# MIPI.net
KiCad netlist of a schematic drawn in Altium Designer
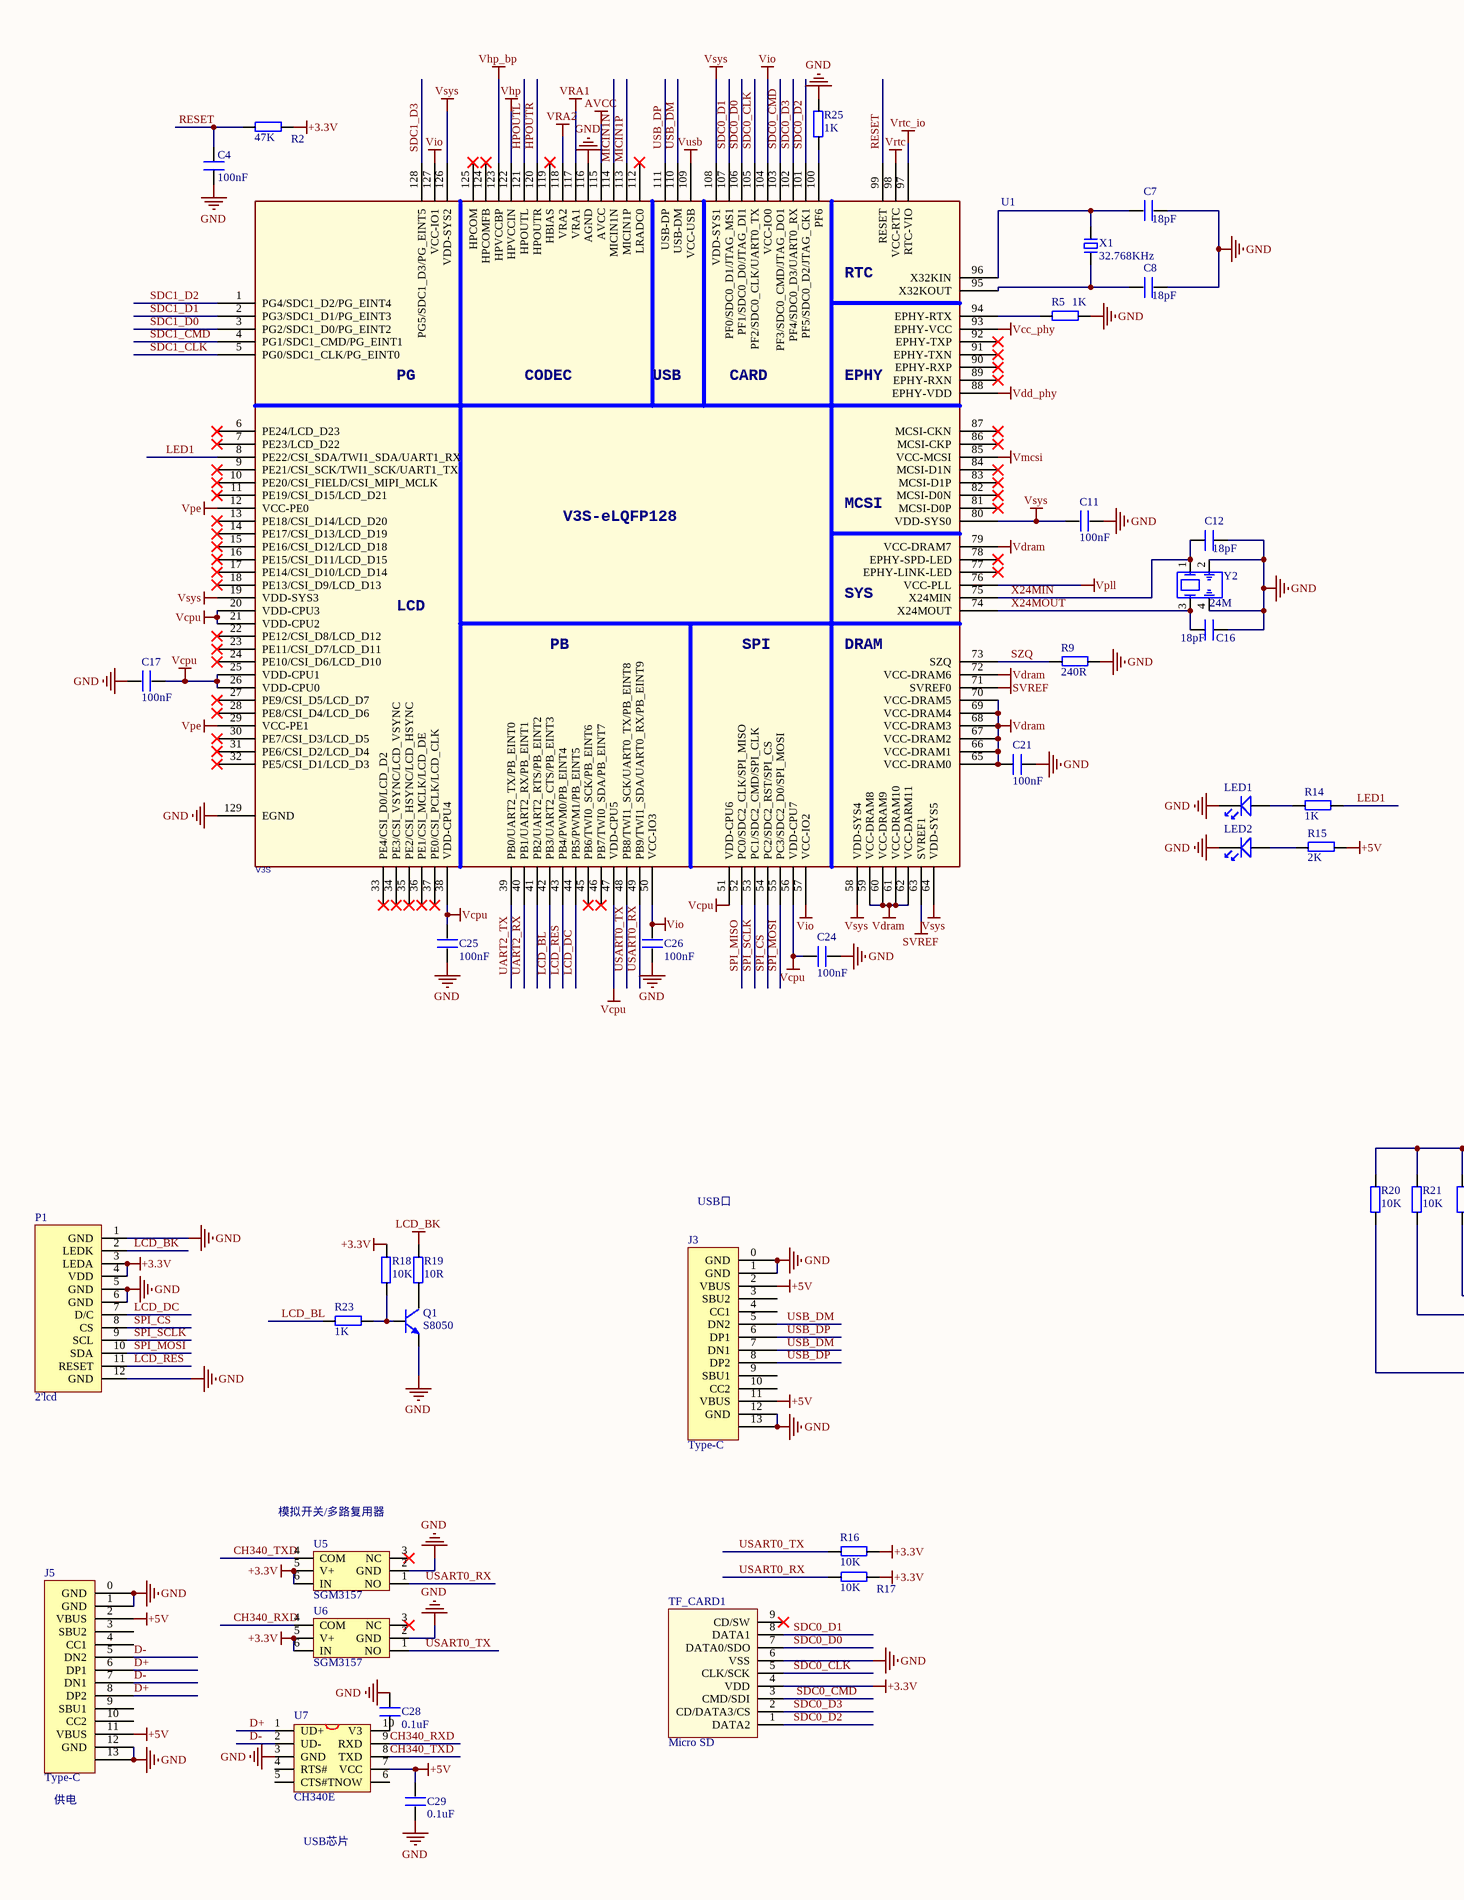
[diagram p0: MIPI.SCHDOC, left]
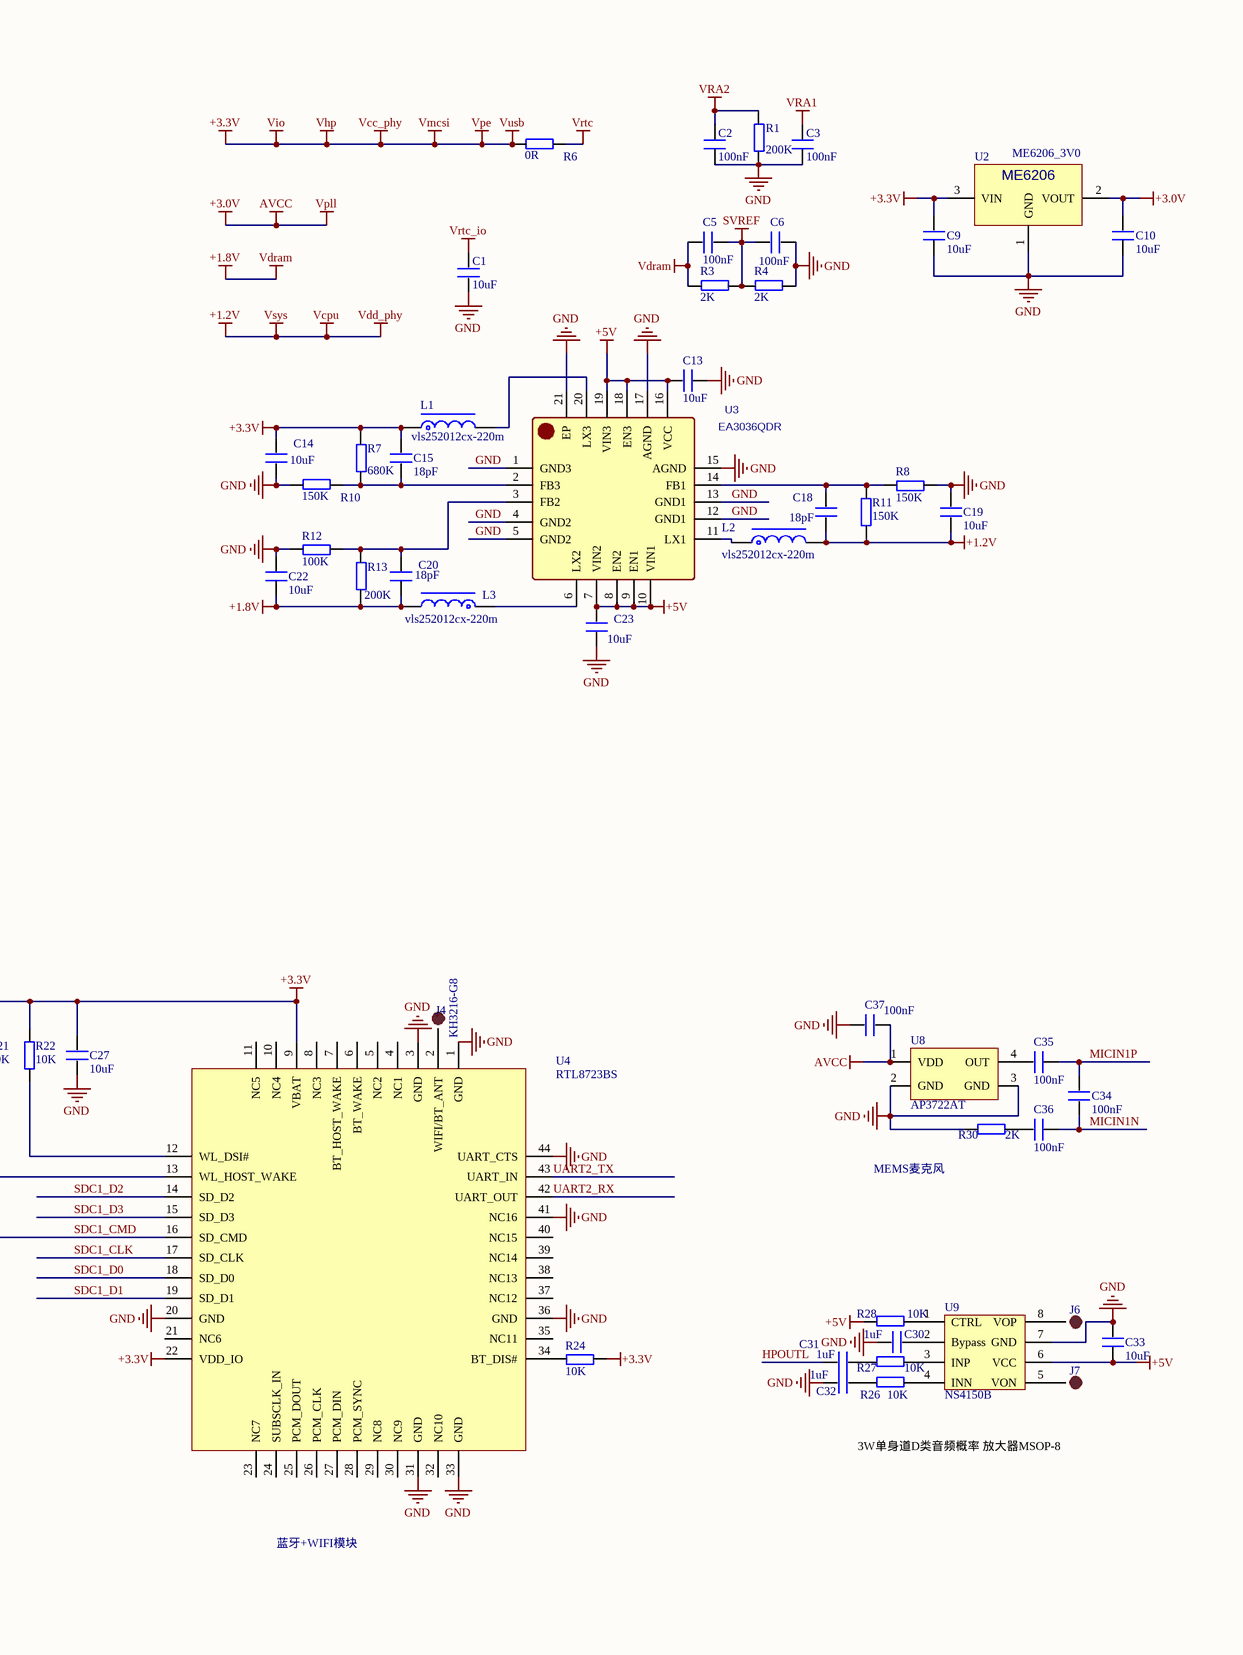
[diagram p1: MIPI.SCHDOC, right]

(export (version "E")
  (design (tool "Eeschema 10.0.6"))
  (components
    (comp (ref "C1") (value "10uF") (footprint "0603") (libsource (lib "AltiumLib") (part "C")))
    (comp (ref "C2") (value "100nF") (footprint "0402") (libsource (lib "AltiumLib") (part "C")))
    (comp (ref "C3") (value "100nF") (footprint "0402") (libsource (lib "AltiumLib") (part "C")))
    (comp (ref "C4") (value "100nF") (footprint "0402") (libsource (lib "AltiumLib") (part "C")))
    (comp (ref "C5") (value "100nF") (footprint "0402") (libsource (lib "AltiumLib") (part "C")))
    (comp (ref "C6") (value "100nF") (footprint "0402") (libsource (lib "AltiumLib") (part "C")))
    (comp (ref "C7") (value "18pF") (footprint "0402") (libsource (lib "AltiumLib") (part "C")))
    (comp (ref "C8") (value "18pF") (footprint "0402") (libsource (lib "AltiumLib") (part "C")))
    (comp (ref "C9") (value "10uF") (footprint "0603") (libsource (lib "AltiumLib") (part "C")))
    (comp (ref "C10") (value "10uF") (footprint "0603") (libsource (lib "AltiumLib") (part "C")))
    (comp (ref "C11") (value "100nF") (footprint "0402") (libsource (lib "AltiumLib") (part "C")))
    (comp (ref "C12") (value "18pF") (footprint "0402") (libsource (lib "AltiumLib") (part "C")))
    (comp (ref "C13") (value "10uF") (footprint "0603") (libsource (lib "AltiumLib") (part "C")))
    (comp (ref "C14") (value "10uF") (footprint "0603") (libsource (lib "AltiumLib") (part "C")))
    (comp (ref "C15") (value "18pF") (footprint "0402") (libsource (lib "AltiumLib") (part "C")))
    (comp (ref "C16") (value "18pF") (footprint "0402") (libsource (lib "AltiumLib") (part "C")))
    (comp (ref "C17") (value "100nF") (footprint "0402") (libsource (lib "AltiumLib") (part "C")))
    (comp (ref "C18") (value "18pF") (footprint "0402") (libsource (lib "AltiumLib") (part "C")))
    (comp (ref "C19") (value "10uF") (footprint "0603") (libsource (lib "AltiumLib") (part "C")))
    (comp (ref "C20") (value "18pF") (footprint "0402") (libsource (lib "AltiumLib") (part "C")))
    (comp (ref "C21") (value "100nF") (footprint "0402") (libsource (lib "AltiumLib") (part "C")))
    (comp (ref "C22") (value "10uF") (footprint "0603") (libsource (lib "AltiumLib") (part "C")))
    (comp (ref "C23") (value "10uF") (footprint "0603") (libsource (lib "AltiumLib") (part "C")))
    (comp (ref "C24") (value "100nF") (footprint "0402") (libsource (lib "AltiumLib") (part "C")))
    (comp (ref "C25") (value "100nF") (footprint "0402") (libsource (lib "AltiumLib") (part "C")))
    (comp (ref "C26") (value "100nF") (footprint "0402") (libsource (lib "AltiumLib") (part "C")))
    (comp (ref "C27") (value "10uF") (footprint "0603") (libsource (lib "AltiumLib") (part "C")))
    (comp (ref "C28") (value "0.1uF") (footprint "0402") (libsource (lib "AltiumLib") (part "C")))
    (comp (ref "C29") (value "0.1uF") (footprint "0402") (libsource (lib "AltiumLib") (part "C")))
    (comp (ref "C30") (value "1uF") (footprint "0402") (libsource (lib "AltiumLib") (part "C")))
    (comp (ref "C31") (value "1uF") (footprint "0402") (libsource (lib "AltiumLib") (part "C")))
    (comp (ref "C32") (value "1uF") (footprint "0402") (libsource (lib "AltiumLib") (part "C")))
    (comp (ref "C33") (value "10uF") (footprint "0603") (libsource (lib "AltiumLib") (part "C")))
    (comp (ref "C34") (value "100nF") (footprint "0402") (libsource (lib "AltiumLib") (part "C")))
    (comp (ref "C35") (value "100nF") (footprint "0402") (libsource (lib "AltiumLib") (part "C")))
    (comp (ref "C36") (value "100nF") (footprint "0402") (libsource (lib "AltiumLib") (part "C")))
    (comp (ref "C37") (value "100nF") (footprint "0402") (libsource (lib "AltiumLib") (part "C")))
    (comp (ref "J3")
      (value "Type-C")
      (footprint "USB-C-SMD_TYC-302-16")
      (libsource (lib "AltiumLib") (part "Type-C_12pin"))
    )
    (comp (ref "J4")
      (value "KH3216-G8")
      (footprint "ANT-SMD_L3.2-W1.6")
      (description "测试点")
      (libsource (lib "AltiumLib") (part "TEST-POINT"))
    )
    (comp (ref "J5")
      (value "Type-C")
      (footprint "USB-C-SMD_TYC-302-16")
      (libsource (lib "AltiumLib") (part "Type-C_12pin"))
    )
    (comp (ref "J6")
      (value "~")
      (footprint "TP-1.5")
      (description "测试点")
      (libsource (lib "AltiumLib") (part "TEST-POINT"))
    )
    (comp (ref "J7")
      (value "~")
      (footprint "TP-1.5")
      (description "测试点")
      (libsource (lib "AltiumLib") (part "TEST-POINT"))
    )
    (comp (ref "L1")
      (value "vls252012cx-220m")
      (footprint "L1")
      (description "功率屏蔽电感")
      (libsource (lib "AltiumLib") (part "L-CDRH"))
    )
    (comp (ref "L2")
      (value "vls252012cx-220m")
      (footprint "L1")
      (description "功率屏蔽电感")
      (libsource (lib "AltiumLib") (part "L-CDRH"))
    )
    (comp (ref "L3")
      (value "vls252012cx-220m")
      (footprint "L1")
      (description "功率屏蔽电感")
      (libsource (lib "") (part "L-CDRH_1"))
    )
    (comp (ref "LED1") (value "LED") (footprint "0603") (libsource (lib "AltiumLib") (part "LED")))
    (comp (ref "LED2") (value "LED") (footprint "0603") (libsource (lib "AltiumLib") (part "LED")))
    (comp (ref "P1") (value "2'lcd") (footprint "2'LCD") (libsource (lib "AltiumLib") (part "2'lcd")))
    (comp (ref "Q1")
      (value "S8050")
      (footprint "SOT23-3L")
      (description "高频放大-NPN型")
      (libsource (lib "AltiumLib") (part "8050-SMD"))
    )
    (comp (ref "R1") (value "200K") (footprint "0402") (libsource (lib "AltiumLib") (part "R")))
    (comp (ref "R2") (value "47K") (footprint "0402") (libsource (lib "AltiumLib") (part "R")))
    (comp (ref "R3") (value "2K") (footprint "0402") (libsource (lib "AltiumLib") (part "R")))
    (comp (ref "R4") (value "2K") (footprint "0402") (libsource (lib "AltiumLib") (part "R")))
    (comp (ref "R5") (value "1K") (footprint "0402") (libsource (lib "AltiumLib") (part "R")))
    (comp (ref "R6") (value "0R") (footprint "0402") (libsource (lib "AltiumLib") (part "R")))
    (comp (ref "R7") (value "680K") (footprint "0402") (libsource (lib "AltiumLib") (part "R")))
    (comp (ref "R8") (value "150K") (footprint "0402") (libsource (lib "AltiumLib") (part "R")))
    (comp (ref "R9") (value "240R") (footprint "0402") (libsource (lib "AltiumLib") (part "R")))
    (comp (ref "R10") (value "150K") (footprint "0402") (libsource (lib "AltiumLib") (part "R")))
    (comp (ref "R11") (value "150K") (footprint "0402") (libsource (lib "AltiumLib") (part "R")))
    (comp (ref "R12") (value "100K") (footprint "0402") (libsource (lib "AltiumLib") (part "R")))
    (comp (ref "R13") (value "200K") (footprint "0402") (libsource (lib "AltiumLib") (part "R")))
    (comp (ref "R14") (value "1K") (footprint "0402") (libsource (lib "AltiumLib") (part "R")))
    (comp (ref "R15") (value "2K") (footprint "0402") (libsource (lib "AltiumLib") (part "R")))
    (comp (ref "R16") (value "10K") (footprint "0402") (libsource (lib "AltiumLib") (part "R")))
    (comp (ref "R17") (value "10K") (footprint "0402") (libsource (lib "AltiumLib") (part "R")))
    (comp (ref "R18") (value "10K") (footprint "0402") (libsource (lib "AltiumLib") (part "R")))
    (comp (ref "R19") (value "10R") (footprint "0603") (libsource (lib "AltiumLib") (part "R")))
    (comp (ref "R20") (value "10K") (footprint "0402") (libsource (lib "AltiumLib") (part "R")))
    (comp (ref "R21") (value "10K") (footprint "0402") (libsource (lib "AltiumLib") (part "R")))
    (comp (ref "R22") (value "10K") (footprint "0402") (libsource (lib "AltiumLib") (part "R")))
    (comp (ref "R23") (value "1K") (footprint "0402") (libsource (lib "AltiumLib") (part "R")))
    (comp (ref "R24") (value "10K") (footprint "0402") (libsource (lib "AltiumLib") (part "R")))
    (comp (ref "R25") (value "1K") (footprint "0402") (libsource (lib "AltiumLib") (part "R")))
    (comp (ref "R26") (value "10K") (footprint "0402") (libsource (lib "AltiumLib") (part "R")))
    (comp (ref "R27") (value "10K") (footprint "0402") (libsource (lib "AltiumLib") (part "R")))
    (comp (ref "R28") (value "10K") (footprint "0402") (libsource (lib "AltiumLib") (part "R")))
    (comp (ref "R30") (value "2K") (footprint "0402") (libsource (lib "AltiumLib") (part "R")))
    (comp (ref "TF_CARD1")
      (value "Micro SD")
      (footprint "Micro SD")
      (description "Micro SD卡")
      (libsource (lib "AltiumLib") (part "Micro SD"))
    )
    (comp (ref "U1") (value "V3S") (footprint "LQFP-128") (libsource (lib "AltiumLib") (part "V3S")))
    (comp (ref "U2") (value "ME6206_3V0") (footprint "SOT-23") (libsource (lib "AltiumLib") (part "ME6206")))
    (comp (ref "U3")
      (value "EA3036QDR")
      (footprint "TQFN-20")
      (fields (field (name "BOM_SUPPLIER PART") "C111587"))
      (libsource (lib "AltiumLib") (part "EA3036QDR"))
    )
    (comp (ref "U4")
      (value "RTL8723BS")
      (footprint "RTL8723BS")
      (libsource (lib "AltiumLib") (part "RTL8723BS"))
    )
    (comp (ref "U5")
      (value "SGM3157")
      (footprint "SOT363-6L")
      (description "单路双掷模拟开关")
      (libsource (lib "imx6ull_bb") (part "SGM3157"))
    )
    (comp (ref "U6")
      (value "SGM3157")
      (footprint "SOT363-6L")
      (description "单路双掷模拟开关")
      (libsource (lib "imx6ull_bb") (part "SGM3157"))
    )
    (comp (ref "U7")
      (value "CH340E")
      (footprint "MSOP-10")
      (description "USB2UART")
      (libsource (lib "AltiumLib") (part "CH340E"))
    )
    (comp (ref "U8")
      (value "AP3722AT")
      (footprint "AP3722AT")
      (libsource (lib "AltiumLib") (part "AP3722AT"))
    )
    (comp (ref "U9") (value "NS4150B") (footprint "MSOP8") (libsource (lib "AltiumLib") (part "NS4150B")))
    (comp (ref "X1")
      (value "32.768KHz")
      (footprint "XT_3215_2")
      (description "2脚无源晶振")
      (libsource (lib "AltiumLib") (part "XTAL-2P"))
    )
    (comp (ref "Y2") (value "24M") (footprint "X3225") (libsource (lib "AltiumLib") (part "SMD XTAL")))
  )
  (nets
    (net (code "1") (name "+1.2V") (class "Default")
      (node (ref "C11") (pin "2") (pintype "passive"))
      (node (ref "C17") (pin "1") (pintype "passive"))
      (node (ref "C18") (pin "2") (pintype "passive"))
      (node (ref "C19") (pin "2") (pintype "passive"))
      (node (ref "C24") (pin "2") (pintype "passive"))
      (node (ref "C25") (pin "1") (pintype "passive"))
      (node (ref "L2") (pin "2") (pinfunction "2_2") (pintype "passive"))
      (node (ref "R11") (pin "2") (pintype "passive"))
      (node (ref "U1") (pin "108") (pinfunction "VDD-SYS1_108") (pintype "passive"))
      (node (ref "U1") (pin "126") (pinfunction "VDD-SYS2_126") (pintype "passive"))
      (node (ref "U1") (pin "19") (pinfunction "VDD-SYS3_19") (pintype "passive"))
      (node (ref "U1") (pin "20") (pinfunction "VDD-CPU3_20") (pintype "passive"))
      (node (ref "U1") (pin "21") (pinfunction "VDD-CPU2_21") (pintype "passive"))
      (node (ref "U1") (pin "25") (pinfunction "VDD-CPU1_25") (pintype "passive"))
      (node (ref "U1") (pin "26") (pinfunction "VDD-CPU0_26") (pintype "passive"))
      (node (ref "U1") (pin "38") (pinfunction "VDD-CPU4_38") (pintype "passive"))
      (node (ref "U1") (pin "47") (pinfunction "VDD-CPU5_47") (pintype "passive"))
      (node (ref "U1") (pin "51") (pinfunction "VDD-CPU6_51") (pintype "passive"))
      (node (ref "U1") (pin "56") (pinfunction "VDD-CPU7_56") (pintype "passive"))
      (node (ref "U1") (pin "58") (pinfunction "VDD-SYS4_58") (pintype "passive"))
      (node (ref "U1") (pin "64") (pinfunction "VDD-SYS5_64") (pintype "passive"))
      (node (ref "U1") (pin "80") (pinfunction "VDD-SYS0_80") (pintype "passive"))
      (node (ref "U1") (pin "88") (pinfunction "EPHY-VDD_88") (pintype "passive"))
    )
    (net (code "2") (name "+1.8V") (class "Default")
      (node (ref "C20") (pin "2") (pintype "passive"))
      (node (ref "C21") (pin "2") (pintype "passive"))
      (node (ref "C22") (pin "2") (pintype "passive"))
      (node (ref "C5") (pin "2") (pintype "passive"))
      (node (ref "L3") (pin "2") (pinfunction "2_2") (pintype "passive"))
      (node (ref "R13") (pin "2") (pintype "passive"))
      (node (ref "R3") (pin "2") (pintype "passive"))
      (node (ref "U1") (pin "59") (pinfunction "VCC-DRAM8_59") (pintype "passive"))
      (node (ref "U1") (pin "60") (pinfunction "VCC-DRAM9_60") (pintype "passive"))
      (node (ref "U1") (pin "61") (pinfunction "VCC-DRAM10_61") (pintype "passive"))
      (node (ref "U1") (pin "62") (pinfunction "VCC-DARM11_62") (pintype "passive"))
      (node (ref "U1") (pin "65") (pinfunction "VCC-DRAM0_65") (pintype "passive"))
      (node (ref "U1") (pin "66") (pinfunction "VCC-DRAM1_66") (pintype "passive"))
      (node (ref "U1") (pin "67") (pinfunction "VCC-DRAM2_67") (pintype "passive"))
      (node (ref "U1") (pin "68") (pinfunction "VCC-DRAM3_68") (pintype "passive"))
      (node (ref "U1") (pin "69") (pinfunction "VCC-DRAM4_69") (pintype "passive"))
      (node (ref "U1") (pin "70") (pinfunction "VCC-DRAM5_70") (pintype "passive"))
      (node (ref "U1") (pin "72") (pinfunction "VCC-DRAM6_72") (pintype "passive"))
      (node (ref "U1") (pin "79") (pinfunction "VCC-DRAM7_79") (pintype "passive"))
    )
    (net (code "3") (name "+3.0V") (class "Default")
      (node (ref "C10") (pin "1") (pintype "passive"))
      (node (ref "C37") (pin "1") (pintype "passive"))
      (node (ref "U1") (pin "115") (pinfunction "AVCC_115") (pintype "passive"))
      (node (ref "U1") (pin "76") (pinfunction "VCC-PLL_76") (pintype "passive"))
      (node (ref "U2") (pin "2") (pinfunction "VOUT_2") (pintype "power_in"))
      (node (ref "U8") (pin "1") (pinfunction "VDD_1") (pintype "passive"))
    )
    (net (code "4") (name "+3.3V") (class "Default")
      (node (ref "C14") (pin "2") (pintype "passive"))
      (node (ref "C15") (pin "2") (pintype "passive"))
      (node (ref "C26") (pin "2") (pintype "passive"))
      (node (ref "C27") (pin "1") (pintype "passive"))
      (node (ref "C9") (pin "1") (pintype "passive"))
      (node (ref "L1") (pin "1") (pinfunction "1_1") (pintype "passive"))
      (node (ref "P1") (pin "3") (pinfunction "LEDA_3") (pintype "passive"))
      (node (ref "P1") (pin "4") (pinfunction "VDD_4") (pintype "passive"))
      (node (ref "R16") (pin "1") (pintype "passive"))
      (node (ref "R17") (pin "1") (pintype "passive"))
      (node (ref "R18") (pin "1") (pintype "passive"))
      (node (ref "R2") (pin "1") (pintype "passive"))
      (node (ref "R20") (pin "1") (pintype "passive"))
      (node (ref "R21") (pin "1") (pintype "passive"))
      (node (ref "R22") (pin "1") (pintype "passive"))
      (node (ref "R24") (pin "2") (pintype "passive"))
      (node (ref "R6") (pin "2") (pintype "passive"))
      (node (ref "R7") (pin "2") (pintype "passive"))
      (node (ref "TF_CARD1") (pin "4") (pinfunction "VDD_4") (pintype "passive"))
      (node (ref "U1") (pin "104") (pinfunction "VCC-IO0_104") (pintype "passive"))
      (node (ref "U1") (pin "109") (pinfunction "VCC-USB_109") (pintype "passive"))
      (node (ref "U1") (pin "12") (pinfunction "VCC-PE0_12") (pintype "passive"))
      (node (ref "U1") (pin "122") (pinfunction "HPVCCIN_122") (pintype "passive"))
      (node (ref "U1") (pin "127") (pinfunction "VCC-IO1_127") (pintype "passive"))
      (node (ref "U1") (pin "29") (pinfunction "VCC-PE1_29") (pintype "passive"))
      (node (ref "U1") (pin "50") (pinfunction "VCC-IO3_50") (pintype "passive"))
      (node (ref "U1") (pin "57") (pinfunction "VCC-IO2_57") (pintype "passive"))
      (node (ref "U1") (pin "85") (pinfunction "VCC-MCSI_85") (pintype "passive"))
      (node (ref "U1") (pin "93") (pinfunction "EPHY-VCC_93") (pintype "passive"))
      (node (ref "U2") (pin "3") (pinfunction "VIN_3") (pintype "power_in"))
      (node (ref "U4") (pin "22") (pinfunction "VDD_IO_22") (pintype "passive"))
      (node (ref "U4") (pin "9") (pinfunction "VBAT_9") (pintype "passive"))
      (node (ref "U5") (pin "5") (pinfunction "V+_5") (pintype "passive"))
      (node (ref "U5") (pin "6") (pinfunction "IN_6") (pintype "passive"))
      (node (ref "U6") (pin "5") (pinfunction "V+_5") (pintype "passive"))
      (node (ref "U6") (pin "6") (pinfunction "IN_6") (pintype "passive"))
    )
    (net (code "5") (name "+5V") (class "Default")
      (node (ref "C13") (pin "2") (pintype "passive"))
      (node (ref "C23") (pin "2") (pintype "passive"))
      (node (ref "C29") (pin "2") (pintype "passive"))
      (node (ref "C33") (pin "1") (pintype "passive"))
      (node (ref "J3") (pin "11") (pinfunction "VBUS_11") (pintype "passive"))
      (node (ref "J3") (pin "2") (pinfunction "VBUS_2") (pintype "passive"))
      (node (ref "J5") (pin "11") (pinfunction "VBUS_11") (pintype "passive"))
      (node (ref "J5") (pin "2") (pinfunction "VBUS_2") (pintype "passive"))
      (node (ref "R15") (pin "1") (pintype "passive"))
      (node (ref "R28") (pin "2") (pintype "passive"))
      (node (ref "U3") (pin "10") (pinfunction "VIN1_10") (pintype "passive"))
      (node (ref "U3") (pin "16") (pinfunction "VCC_16") (pintype "passive"))
      (node (ref "U3") (pin "18") (pinfunction "EN3_18") (pintype "passive"))
      (node (ref "U3") (pin "19") (pinfunction "VIN3_19") (pintype "passive"))
      (node (ref "U3") (pin "7") (pinfunction "VIN2_7") (pintype "passive"))
      (node (ref "U3") (pin "8") (pinfunction "EN2_8") (pintype "passive"))
      (node (ref "U3") (pin "9") (pinfunction "EN1_9") (pintype "passive"))
      (node (ref "U7") (pin "7") (pinfunction "VCC_7") (pintype "passive"))
      (node (ref "U9") (pin "6") (pinfunction "VCC_6") (pintype "passive"))
    )
    (net (code "6") (name "/CH340_RXD") (class "Default")
      (node (ref "U6") (pin "4") (pinfunction "COM_4") (pintype "passive"))
      (node (ref "U7") (pin "9") (pinfunction "RXD_9") (pintype "passive"))
    )
    (net (code "7") (name "/CH340_TXD") (class "Default")
      (node (ref "U5") (pin "4") (pinfunction "COM_4") (pintype "passive"))
      (node (ref "U7") (pin "8") (pinfunction "TXD_8") (pintype "passive"))
    )
    (net (code "8") (name "/D+") (class "Default")
      (node (ref "J5") (pin "6") (pinfunction "DP1_6") (pintype "passive"))
      (node (ref "J5") (pin "8") (pinfunction "DP2_8") (pintype "passive"))
      (node (ref "U7") (pin "1") (pinfunction "UD+_1") (pintype "passive"))
    )
    (net (code "9") (name "/D-") (class "Default")
      (node (ref "J5") (pin "5") (pinfunction "DN2_5") (pintype "passive"))
      (node (ref "J5") (pin "7") (pinfunction "DN1_7") (pintype "passive"))
      (node (ref "U7") (pin "2") (pinfunction "UD-_2") (pintype "passive"))
    )
    (net (code "10") (name "/HPOUTL") (class "Default")
      (node (ref "C31") (pin "2") (pintype "passive"))
      (node (ref "U1") (pin "121") (pinfunction "HPOUTL_121") (pintype "passive"))
    )
    (net (code "11") (name "/HPOUTR") (class "Default")
      (node (ref "U1") (pin "120") (pinfunction "HPOUTR_120") (pintype "passive"))
    )
    (net (code "12") (name "/LCD_BL") (class "Default")
      (node (ref "R23") (pin "2") (pintype "passive"))
      (node (ref "U1") (pin "42") (pinfunction "PB3/UART2_CTS/PB_EINT3_42") (pintype "passive"))
    )
    (net (code "13") (name "/LCD_DC") (class "Default")
      (node (ref "P1") (pin "7") (pinfunction "D/C_7") (pintype "passive"))
      (node (ref "U1") (pin "44") (pinfunction "PB5/PWM1/PB_EINT5_44") (pintype "passive"))
    )
    (net (code "14") (name "/LCD_RES") (class "Default")
      (node (ref "P1") (pin "11") (pinfunction "RESET_11") (pintype "passive"))
      (node (ref "U1") (pin "43") (pinfunction "PB4/PWM0/PB_EINT4_43") (pintype "passive"))
    )
    (net (code "15") (name "/LED1") (class "Default")
      (node (ref "R14") (pin "1") (pintype "passive"))
      (node (ref "U1") (pin "8") (pinfunction "PE22/CSI_SDA/TWI1_SDA/UART1_RX_8") (pintype "passive"))
    )
    (net (code "16") (name "/MICIN1N") (class "Default")
      (node (ref "C34") (pin "2") (pintype "passive"))
      (node (ref "C36") (pin "2") (pintype "passive"))
      (node (ref "U1") (pin "114") (pinfunction "MICIN1N_114") (pintype "passive"))
    )
    (net (code "17") (name "/MICIN1P") (class "Default")
      (node (ref "C34") (pin "1") (pintype "passive"))
      (node (ref "C35") (pin "2") (pintype "passive"))
      (node (ref "U1") (pin "113") (pinfunction "MICIN1P_113") (pintype "passive"))
    )
    (net (code "18") (name "/RESET") (class "Default")
      (node (ref "C4") (pin "2") (pintype "passive"))
      (node (ref "R2") (pin "2") (pintype "passive"))
      (node (ref "U1") (pin "99") (pinfunction "RESET_99") (pintype "passive"))
    )
    (net (code "19") (name "/SDC0_CLK") (class "Default")
      (node (ref "TF_CARD1") (pin "5") (pinfunction "CLK/SCK_5") (pintype "passive"))
      (node (ref "U1") (pin "105") (pinfunction "PF2/SDC0_CLK/UART0_TX_105") (pintype "passive"))
    )
    (net (code "20") (name "/SDC0_CMD") (class "Default")
      (node (ref "TF_CARD1") (pin "3") (pinfunction "CMD/SDI_3") (pintype "passive"))
      (node (ref "U1") (pin "103") (pinfunction "PF3/SDC0_CMD/JTAG_DO1_103") (pintype "passive"))
    )
    (net (code "21") (name "/SDC0_D0") (class "Default")
      (node (ref "TF_CARD1") (pin "7") (pinfunction "DATA0/SDO_7") (pintype "passive"))
      (node (ref "U1") (pin "106") (pinfunction "PF1/SDC0_D0/JTAG_DI1_106") (pintype "passive"))
    )
    (net (code "22") (name "/SDC0_D1") (class "Default")
      (node (ref "TF_CARD1") (pin "8") (pinfunction "DATA1_8") (pintype "passive"))
      (node (ref "U1") (pin "107") (pinfunction "PF0/SDC0_D1/JTAG_MS1_107") (pintype "passive"))
    )
    (net (code "23") (name "/SDC0_D2") (class "Default")
      (node (ref "TF_CARD1") (pin "1") (pinfunction "DATA2_1") (pintype "passive"))
      (node (ref "U1") (pin "101") (pinfunction "PF5/SDC0_D2/JTAG_CK1_101") (pintype "passive"))
    )
    (net (code "24") (name "/SDC0_D3") (class "Default")
      (node (ref "TF_CARD1") (pin "2") (pinfunction "CD/DATA3/CS_2") (pintype "passive"))
      (node (ref "U1") (pin "102") (pinfunction "PF4/SDC0_D3/UART0_RX_102") (pintype "passive"))
    )
    (net (code "25") (name "/SDC1_CLK") (class "Default")
      (node (ref "U1") (pin "5") (pinfunction "PG0/SDC1_CLK/PG_EINT0_5") (pintype "passive"))
      (node (ref "U4") (pin "17") (pinfunction "SD_CLK_17") (pintype "passive"))
    )
    (net (code "26") (name "/SDC1_CMD") (class "Default")
      (node (ref "R20") (pin "2") (pintype "passive"))
      (node (ref "U1") (pin "4") (pinfunction "PG1/SDC1_CMD/PG_EINT1_4") (pintype "passive"))
      (node (ref "U4") (pin "16") (pinfunction "SD_CMD_16") (pintype "passive"))
    )
    (net (code "27") (name "/SDC1_D0") (class "Default")
      (node (ref "U1") (pin "3") (pinfunction "PG2/SDC1_D0/PG_EINT2_3") (pintype "passive"))
      (node (ref "U4") (pin "18") (pinfunction "SD_D0_18") (pintype "passive"))
    )
    (net (code "28") (name "/SDC1_D1") (class "Default")
      (node (ref "U1") (pin "2") (pinfunction "PG3/SDC1_D1/PG_EINT3_2") (pintype "passive"))
      (node (ref "U4") (pin "19") (pinfunction "SD_D1_19") (pintype "passive"))
    )
    (net (code "29") (name "/SDC1_D2") (class "Default")
      (node (ref "U1") (pin "1") (pinfunction "PG4/SDC1_D2/PG_EINT4_1") (pintype "passive"))
      (node (ref "U4") (pin "14") (pinfunction "SD_D2_14") (pintype "passive"))
    )
    (net (code "30") (name "/SDC1_D3") (class "Default")
      (node (ref "U1") (pin "128") (pinfunction "PG5/SDC1_D3/PG_EINT5_128") (pintype "passive"))
      (node (ref "U4") (pin "15") (pinfunction "SD_D3_15") (pintype "passive"))
    )
    (net (code "31") (name "/SPI_CS") (class "Default")
      (node (ref "P1") (pin "8") (pinfunction "CS_8") (pintype "passive"))
      (node (ref "U1") (pin "54") (pinfunction "PC2/SDC2_RST/SPI_CS_54") (pintype "passive"))
    )
    (net (code "32") (name "/SPI_MISO") (class "Default")
      (node (ref "U1") (pin "52") (pinfunction "PC0/SDC2_CLK/SPI_MISO_52") (pintype "passive"))
    )
    (net (code "33") (name "/SPI_MOSI") (class "Default")
      (node (ref "P1") (pin "10") (pinfunction "SDA_10") (pintype "passive"))
      (node (ref "U1") (pin "55") (pinfunction "PC3/SDC2_D0/SPI_MOSI_55") (pintype "passive"))
    )
    (net (code "34") (name "/SPI_SCLK") (class "Default")
      (node (ref "P1") (pin "9") (pinfunction "SCL_9") (pintype "passive"))
      (node (ref "U1") (pin "53") (pinfunction "PC1/SDC2_CMD/SPI_CLK_53") (pintype "passive"))
    )
    (net (code "35") (name "/SZQ") (class "Default")
      (node (ref "R9") (pin "2") (pintype "passive"))
      (node (ref "U1") (pin "73") (pinfunction "SZQ_73") (pintype "passive"))
    )
    (net (code "36") (name "/UART2_RX") (class "Default")
      (node (ref "U1") (pin "40") (pinfunction "PB1/UART2_RX/PB_EINT1_40") (pintype "passive"))
      (node (ref "U4") (pin "42") (pinfunction "UART_OUT_42") (pintype "passive"))
    )
    (net (code "37") (name "/UART2_TX") (class "Default")
      (node (ref "U1") (pin "39") (pinfunction "PB0/UART2_TX/PB_EINT0_39") (pintype "passive"))
      (node (ref "U4") (pin "43") (pinfunction "UART_IN_43") (pintype "passive"))
    )
    (net (code "38") (name "/USART0_RX") (class "Default")
      (node (ref "R17") (pin "2") (pintype "passive"))
      (node (ref "U1") (pin "49") (pinfunction "PB9/TWI1_SDA/UART0_RX/PB_EINT9_49") (pintype "passive"))
      (node (ref "U5") (pin "1") (pinfunction "NO_1") (pintype "passive"))
    )
    (net (code "39") (name "/USART0_TX") (class "Default")
      (node (ref "R16") (pin "2") (pintype "passive"))
      (node (ref "U1") (pin "48") (pinfunction "PB8/TWI1_SCK/UART0_TX/PB_EINT8_48") (pintype "passive"))
      (node (ref "U6") (pin "1") (pinfunction "NO_1") (pintype "passive"))
    )
    (net (code "40") (name "/USB_DM") (class "Default")
      (node (ref "J3") (pin "5") (pinfunction "DN2_5") (pintype "passive"))
      (node (ref "J3") (pin "7") (pinfunction "DN1_7") (pintype "passive"))
      (node (ref "U1") (pin "110") (pinfunction "USB-DM_110") (pintype "passive"))
    )
    (net (code "41") (name "/USB_DP") (class "Default")
      (node (ref "J3") (pin "6") (pinfunction "DP1_6") (pintype "passive"))
      (node (ref "J3") (pin "8") (pinfunction "DP2_8") (pintype "passive"))
      (node (ref "U1") (pin "111") (pinfunction "USB-DP_111") (pintype "passive"))
    )
    (net (code "42") (name "/X24MIN") (class "Default")
      (node (ref "C12") (pin "1") (pintype "passive"))
      (node (ref "U1") (pin "75") (pinfunction "X24MIN_75") (pintype "passive"))
      (node (ref "Y2") (pin "1") (pinfunction "OSC1_1") (pintype "passive"))
    )
    (net (code "43") (name "/X24MOUT") (class "Default")
      (node (ref "C16") (pin "1") (pintype "passive"))
      (node (ref "U1") (pin "74") (pinfunction "X24MOUT_74") (pintype "passive"))
      (node (ref "Y2") (pin "3") (pinfunction "OSC2_3") (pintype "passive"))
    )
    (net (code "44") (name "GND") (class "Default")
      (node (ref "C1") (pin "2") (pintype "passive"))
      (node (ref "C10") (pin "2") (pintype "passive"))
      (node (ref "C11") (pin "1") (pintype "passive"))
      (node (ref "C12") (pin "2") (pintype "passive"))
      (node (ref "C13") (pin "1") (pintype "passive"))
      (node (ref "C14") (pin "1") (pintype "passive"))
      (node (ref "C16") (pin "2") (pintype "passive"))
      (node (ref "C17") (pin "2") (pintype "passive"))
      (node (ref "C19") (pin "1") (pintype "passive"))
      (node (ref "C2") (pin "1") (pintype "passive"))
      (node (ref "C21") (pin "1") (pintype "passive"))
      (node (ref "C22") (pin "1") (pintype "passive"))
      (node (ref "C23") (pin "1") (pintype "passive"))
      (node (ref "C24") (pin "1") (pintype "passive"))
      (node (ref "C25") (pin "2") (pintype "passive"))
      (node (ref "C26") (pin "1") (pintype "passive"))
      (node (ref "C27") (pin "2") (pintype "passive"))
      (node (ref "C28") (pin "2") (pintype "passive"))
      (node (ref "C29") (pin "1") (pintype "passive"))
      (node (ref "C3") (pin "1") (pintype "passive"))
      (node (ref "C30") (pin "2") (pintype "passive"))
      (node (ref "C32") (pin "2") (pintype "passive"))
      (node (ref "C33") (pin "2") (pintype "passive"))
      (node (ref "C37") (pin "2") (pintype "passive"))
      (node (ref "C4") (pin "1") (pintype "passive"))
      (node (ref "C6") (pin "1") (pintype "passive"))
      (node (ref "C7") (pin "2") (pintype "passive"))
      (node (ref "C8") (pin "2") (pintype "passive"))
      (node (ref "C9") (pin "2") (pintype "passive"))
      (node (ref "J3") (pin "0") (pinfunction "GND_0") (pintype "passive"))
      (node (ref "J3") (pin "1") (pinfunction "GND_1") (pintype "passive"))
      (node (ref "J3") (pin "12") (pinfunction "GND_12") (pintype "passive"))
      (node (ref "J3") (pin "13") (pintype "passive"))
      (node (ref "J5") (pin "0") (pinfunction "GND_0") (pintype "passive"))
      (node (ref "J5") (pin "1") (pinfunction "GND_1") (pintype "passive"))
      (node (ref "J5") (pin "12") (pinfunction "GND_12") (pintype "passive"))
      (node (ref "J5") (pin "13") (pintype "passive"))
      (node (ref "LED1") (pin "2") (pinfunction "2_2") (pintype "passive"))
      (node (ref "LED2") (pin "2") (pinfunction "2_2") (pintype "passive"))
      (node (ref "P1") (pin "1") (pinfunction "GND_1") (pintype "passive"))
      (node (ref "P1") (pin "12") (pinfunction "GND_12") (pintype "passive"))
      (node (ref "P1") (pin "5") (pinfunction "GND_5") (pintype "passive"))
      (node (ref "P1") (pin "6") (pinfunction "GND_6") (pintype "passive"))
      (node (ref "Q1") (pin "2") (pinfunction "E_2") (pintype "passive"))
      (node (ref "R1") (pin "1") (pintype "passive"))
      (node (ref "R10") (pin "2") (pintype "passive"))
      (node (ref "R12") (pin "2") (pintype "passive"))
      (node (ref "R25") (pin "1") (pintype "passive"))
      (node (ref "R30") (pin "2") (pintype "passive"))
      (node (ref "R4") (pin "1") (pintype "passive"))
      (node (ref "R5") (pin "1") (pintype "passive"))
      (node (ref "R8") (pin "2") (pintype "passive"))
      (node (ref "R9") (pin "1") (pintype "passive"))
      (node (ref "TF_CARD1") (pin "6") (pinfunction "VSS_6") (pintype "passive"))
      (node (ref "U1") (pin "116") (pinfunction "AGND_116") (pintype "passive"))
      (node (ref "U1") (pin "129") (pinfunction "EGND_129") (pintype "passive"))
      (node (ref "U2") (pin "1") (pinfunction "GND_1") (pintype "power_in"))
      (node (ref "U3") (pin "1") (pinfunction "GND3_1") (pintype "passive"))
      (node (ref "U3") (pin "12") (pinfunction "GND1_12") (pintype "passive"))
      (node (ref "U3") (pin "13") (pinfunction "GND1_13") (pintype "passive"))
      (node (ref "U3") (pin "15") (pinfunction "AGND_15") (pintype "passive"))
      (node (ref "U3") (pin "17") (pinfunction "AGND_17") (pintype "passive"))
      (node (ref "U3") (pin "21") (pinfunction "EP_21") (pintype "passive"))
      (node (ref "U3") (pin "4") (pinfunction "GND2_4") (pintype "passive"))
      (node (ref "U3") (pin "5") (pinfunction "GND2_5") (pintype "passive"))
      (node (ref "U4") (pin "1") (pinfunction "GND_1") (pintype "passive"))
      (node (ref "U4") (pin "20") (pinfunction "GND_20") (pintype "passive"))
      (node (ref "U4") (pin "3") (pinfunction "GND_3") (pintype "passive"))
      (node (ref "U4") (pin "31") (pinfunction "GND_31") (pintype "passive"))
      (node (ref "U4") (pin "33") (pinfunction "GND_33") (pintype "passive"))
      (node (ref "U4") (pin "36") (pinfunction "GND_36") (pintype "passive"))
      (node (ref "U4") (pin "41") (pinfunction "NC16_41") (pintype "passive"))
      (node (ref "U4") (pin "44") (pinfunction "UART_CTS_44") (pintype "passive"))
      (node (ref "U5") (pin "2") (pinfunction "GND_2") (pintype "passive"))
      (node (ref "U6") (pin "2") (pinfunction "GND_2") (pintype "passive"))
      (node (ref "U7") (pin "3") (pinfunction "GND_3") (pintype "passive"))
      (node (ref "U8") (pin "2") (pinfunction "GND_2") (pintype "passive"))
      (node (ref "U8") (pin "3") (pinfunction "GND_3") (pintype "passive"))
      (node (ref "U9") (pin "7") (pinfunction "GND_7") (pintype "passive"))
      (node (ref "Y2") (pin "2") (pinfunction "GND_2") (pintype "passive"))
      (node (ref "Y2") (pin "4") (pinfunction "GND_4") (pintype "passive"))
    )
    (net (code "45") (name "LCD_BK") (class "Default")
      (node (ref "P1") (pin "2") (pinfunction "LEDK_2") (pintype "passive"))
      (node (ref "R19") (pin "1") (pintype "passive"))
    )
    (net (code "46") (name "Net-(C31-Pad1)") (class "Default")
      (node (ref "C31") (pin "1") (pintype "passive"))
      (node (ref "R27") (pin "2") (pintype "passive"))
    )
    (net (code "47") (name "Net-(C32-Pad1)") (class "Default")
      (node (ref "C32") (pin "1") (pintype "passive"))
      (node (ref "R26") (pin "2") (pintype "passive"))
    )
    (net (code "48") (name "Net-(C36-Pad1)") (class "Default")
      (node (ref "C36") (pin "1") (pintype "passive"))
      (node (ref "R30") (pin "1") (pintype "passive"))
    )
    (net (code "49") (name "Net-(LED1-Pad1)") (class "Default")
      (node (ref "LED1") (pin "1") (pinfunction "1_1") (pintype "passive"))
      (node (ref "R14") (pin "2") (pintype "passive"))
    )
    (net (code "50") (name "Net-(LED2-Pad1)") (class "Default")
      (node (ref "LED2") (pin "1") (pinfunction "1_1") (pintype "passive"))
      (node (ref "R15") (pin "2") (pintype "passive"))
    )
    (net (code "51") (name "Net-(Q1-B)") (class "Default")
      (node (ref "Q1") (pin "1") (pinfunction "B_1") (pintype "passive"))
      (node (ref "R18") (pin "2") (pintype "passive"))
      (node (ref "R23") (pin "1") (pintype "passive"))
    )
    (net (code "52") (name "Net-(Q1-C)") (class "Default")
      (node (ref "Q1") (pin "3") (pinfunction "C_3") (pintype "passive"))
      (node (ref "R19") (pin "2") (pintype "passive"))
    )
    (net (code "53") (name "Net-(U1-EPHY-RTX)") (class "Default")
      (node (ref "R5") (pin "2") (pintype "passive"))
      (node (ref "U1") (pin "94") (pinfunction "EPHY-RTX_94") (pintype "passive"))
    )
    (net (code "54") (name "Net-(U1-PF6)") (class "Default")
      (node (ref "R25") (pin "2") (pintype "passive"))
      (node (ref "U1") (pin "100") (pinfunction "PF6_100") (pintype "passive"))
    )
    (net (code "55") (name "Net-(U1-X32KIN)") (class "Default")
      (node (ref "C7") (pin "1") (pintype "passive"))
      (node (ref "U1") (pin "96") (pinfunction "X32KIN_96") (pintype "passive"))
      (node (ref "X1") (pin "2") (pinfunction "2_2") (pintype "passive"))
    )
    (net (code "56") (name "Net-(U1-X32KOUT)") (class "Default")
      (node (ref "C8") (pin "1") (pintype "passive"))
      (node (ref "U1") (pin "95") (pinfunction "X32KOUT_95") (pintype "passive"))
      (node (ref "X1") (pin "1") (pinfunction "1_1") (pintype "passive"))
    )
    (net (code "57") (name "Net-(U3-FB1)") (class "Default")
      (node (ref "C18") (pin "1") (pintype "passive"))
      (node (ref "R11") (pin "1") (pintype "passive"))
      (node (ref "R8") (pin "1") (pintype "passive"))
      (node (ref "U3") (pin "14") (pinfunction "FB1_14") (pintype "passive"))
    )
    (net (code "58") (name "Net-(U3-FB2)") (class "Default")
      (node (ref "C20") (pin "1") (pintype "passive"))
      (node (ref "R12") (pin "1") (pintype "passive"))
      (node (ref "R13") (pin "1") (pintype "passive"))
      (node (ref "U3") (pin "3") (pinfunction "FB2_3") (pintype "passive"))
    )
    (net (code "59") (name "Net-(U3-FB3)") (class "Default")
      (node (ref "C15") (pin "1") (pintype "passive"))
      (node (ref "R10") (pin "1") (pintype "passive"))
      (node (ref "R7") (pin "1") (pintype "passive"))
      (node (ref "U3") (pin "2") (pinfunction "FB3_2") (pintype "passive"))
    )
    (net (code "60") (name "Net-(U3-LX1)") (class "Default")
      (node (ref "L2") (pin "1") (pinfunction "1_1") (pintype "passive"))
      (node (ref "U3") (pin "11") (pinfunction "LX1_11") (pintype "passive"))
    )
    (net (code "61") (name "Net-(U3-LX2)") (class "Default")
      (node (ref "L3") (pin "1") (pinfunction "1_1") (pintype "passive"))
      (node (ref "U3") (pin "6") (pinfunction "LX2_6") (pintype "passive"))
    )
    (net (code "62") (name "Net-(U3-LX3)") (class "Default")
      (node (ref "L1") (pin "2") (pinfunction "2_2") (pintype "passive"))
      (node (ref "U3") (pin "20") (pinfunction "LX3_20") (pintype "passive"))
    )
    (net (code "63") (name "Net-(U4-BT_DIS#)") (class "Default")
      (node (ref "R24") (pin "1") (pintype "passive"))
      (node (ref "U4") (pin "34") (pinfunction "BT_DIS#_34") (pintype "passive"))
    )
    (net (code "64") (name "Net-(U4-WIFI{slash}BT_ANT)") (class "Default")
      (node (ref "J4") (pin "1") (pinfunction "1_1") (pintype "passive"))
      (node (ref "U4") (pin "2") (pinfunction "WIFI/BT_ANT_2") (pintype "passive"))
    )
    (net (code "65") (name "Net-(U4-WL_DSI#)") (class "Default")
      (node (ref "R22") (pin "2") (pintype "passive"))
      (node (ref "U4") (pin "12") (pinfunction "WL_DSI#_12") (pintype "passive"))
    )
    (net (code "66") (name "Net-(U4-WL_HOST_WAKE)") (class "Default")
      (node (ref "R21") (pin "2") (pintype "passive"))
      (node (ref "U4") (pin "13") (pinfunction "WL_HOST_WAKE_13") (pintype "passive"))
    )
    (net (code "67") (name "Net-(U7-V3)") (class "Default")
      (node (ref "C28") (pin "1") (pintype "passive"))
      (node (ref "U7") (pin "10") (pinfunction "V3_10") (pintype "passive"))
    )
    (net (code "68") (name "Net-(U8-OUT)") (class "Default")
      (node (ref "C35") (pin "1") (pintype "passive"))
      (node (ref "U8") (pin "4") (pinfunction "OUT_4") (pintype "passive"))
    )
    (net (code "69") (name "Net-(U9-Bypass)") (class "Default")
      (node (ref "C30") (pin "1") (pintype "passive"))
      (node (ref "U9") (pin "2") (pinfunction "Bypass_2") (pintype "passive"))
    )
    (net (code "70") (name "Net-(U9-CTRL)") (class "Default")
      (node (ref "R28") (pin "1") (pintype "passive"))
      (node (ref "U9") (pin "1") (pinfunction "CTRL_1") (pintype "passive"))
    )
    (net (code "71") (name "Net-(U9-INN)") (class "Default")
      (node (ref "R26") (pin "1") (pintype "passive"))
      (node (ref "U9") (pin "4") (pinfunction "INN_4") (pintype "passive"))
    )
    (net (code "72") (name "Net-(U9-INP)") (class "Default")
      (node (ref "R27") (pin "1") (pintype "passive"))
      (node (ref "U9") (pin "3") (pinfunction "INP_3") (pintype "passive"))
    )
    (net (code "73") (name "Net-(U9-VON)") (class "Default")
      (node (ref "J7") (pin "1") (pinfunction "1_1") (pintype "passive"))
      (node (ref "U9") (pin "5") (pinfunction "VON_5") (pintype "passive"))
    )
    (net (code "74") (name "Net-(U9-VOP)") (class "Default")
      (node (ref "J6") (pin "1") (pinfunction "1_1") (pintype "passive"))
      (node (ref "U9") (pin "8") (pinfunction "VOP_8") (pintype "passive"))
    )
    (net (code "75") (name "SVREF") (class "Default")
      (node (ref "C5") (pin "1") (pintype "passive"))
      (node (ref "C6") (pin "2") (pintype "passive"))
      (node (ref "R3") (pin "1") (pintype "passive"))
      (node (ref "R4") (pin "2") (pintype "passive"))
      (node (ref "U1") (pin "63") (pinfunction "SVREF1_63") (pintype "passive"))
      (node (ref "U1") (pin "71") (pinfunction "SVREF0_71") (pintype "passive"))
    )
    (net (code "76") (name "VRA1") (class "Default")
      (node (ref "C3") (pin "2") (pintype "passive"))
      (node (ref "U1") (pin "117") (pinfunction "VRA1_117") (pintype "passive"))
    )
    (net (code "77") (name "VRA2") (class "Default")
      (node (ref "C2") (pin "2") (pintype "passive"))
      (node (ref "R1") (pin "2") (pintype "passive"))
      (node (ref "U1") (pin "118") (pinfunction "VRA2_118") (pintype "passive"))
    )
    (net (code "78") (name "Vhp_bp") (class "Default")
      (node (ref "U1") (pin "123") (pinfunction "HPVCCBP_123") (pintype "passive"))
    )
    (net (code "79") (name "Vrtc") (class "Default")
      (node (ref "R6") (pin "1") (pintype "passive"))
      (node (ref "U1") (pin "98") (pinfunction "VCC-RTC_98") (pintype "passive"))
    )
    (net (code "80") (name "Vrtc_io") (class "Default")
      (node (ref "C1") (pin "1") (pintype "passive"))
      (node (ref "U1") (pin "97") (pinfunction "RTC-VIO_97") (pintype "passive"))
    )
    (net (code "81") (name "unconnected-(J3-CC1-Pad4)") (class "Default")
      (node (ref "J3") (pin "4") (pinfunction "CC1_4") (pintype "passive"))
    )
    (net (code "82") (name "unconnected-(J3-CC2-Pad10)") (class "Default")
      (node (ref "J3") (pin "10") (pinfunction "CC2_10") (pintype "passive"))
    )
    (net (code "83") (name "unconnected-(J3-SBU1-Pad9)") (class "Default")
      (node (ref "J3") (pin "9") (pinfunction "SBU1_9") (pintype "passive"))
    )
    (net (code "84") (name "unconnected-(J3-SBU2-Pad3)") (class "Default")
      (node (ref "J3") (pin "3") (pinfunction "SBU2_3") (pintype "passive"))
    )
    (net (code "85") (name "unconnected-(J5-CC1-Pad4)") (class "Default")
      (node (ref "J5") (pin "4") (pinfunction "CC1_4") (pintype "passive"))
    )
    (net (code "86") (name "unconnected-(J5-CC2-Pad10)") (class "Default")
      (node (ref "J5") (pin "10") (pinfunction "CC2_10") (pintype "passive"))
    )
    (net (code "87") (name "unconnected-(J5-SBU1-Pad9)") (class "Default")
      (node (ref "J5") (pin "9") (pinfunction "SBU1_9") (pintype "passive"))
    )
    (net (code "88") (name "unconnected-(J5-SBU2-Pad3)") (class "Default")
      (node (ref "J5") (pin "3") (pinfunction "SBU2_3") (pintype "passive"))
    )
    (net (code "89") (name "unconnected-(TF_CARD1-CD{slash}SW-Pad9)") (class "Default")
      (node (ref "TF_CARD1") (pin "9") (pinfunction "CD/SW_9") (pintype "passive+no_connect"))
    )
    (net (code "90") (name "unconnected-(U1-EPHY-LINK-LED-Pad77)") (class "Default")
      (node (ref "U1") (pin "77") (pinfunction "EPHY-LINK-LED_77") (pintype "passive+no_connect"))
    )
    (net (code "91") (name "unconnected-(U1-EPHY-RXN-Pad89)") (class "Default")
      (node (ref "U1") (pin "89") (pinfunction "EPHY-RXN_89") (pintype "passive+no_connect"))
    )
    (net (code "92") (name "unconnected-(U1-EPHY-RXP-Pad90)") (class "Default")
      (node (ref "U1") (pin "90") (pinfunction "EPHY-RXP_90") (pintype "passive+no_connect"))
    )
    (net (code "93") (name "unconnected-(U1-EPHY-SPD-LED-Pad78)") (class "Default")
      (node (ref "U1") (pin "78") (pinfunction "EPHY-SPD-LED_78") (pintype "passive+no_connect"))
    )
    (net (code "94") (name "unconnected-(U1-EPHY-TXN-Pad91)") (class "Default")
      (node (ref "U1") (pin "91") (pinfunction "EPHY-TXN_91") (pintype "passive+no_connect"))
    )
    (net (code "95") (name "unconnected-(U1-EPHY-TXP-Pad92)") (class "Default")
      (node (ref "U1") (pin "92") (pinfunction "EPHY-TXP_92") (pintype "passive+no_connect"))
    )
    (net (code "96") (name "unconnected-(U1-HBIAS-Pad119)") (class "Default")
      (node (ref "U1") (pin "119") (pinfunction "HBIAS_119") (pintype "passive+no_connect"))
    )
    (net (code "97") (name "unconnected-(U1-HPCOM-Pad125)") (class "Default")
      (node (ref "U1") (pin "125") (pinfunction "HPCOM_125") (pintype "passive+no_connect"))
    )
    (net (code "98") (name "unconnected-(U1-HPCOMFB-Pad124)") (class "Default")
      (node (ref "U1") (pin "124") (pinfunction "HPCOMFB_124") (pintype "passive+no_connect"))
    )
    (net (code "99") (name "unconnected-(U1-LRADC0-Pad112)") (class "Default")
      (node (ref "U1") (pin "112") (pinfunction "LRADC0_112") (pintype "passive+no_connect"))
    )
    (net (code "100") (name "unconnected-(U1-MCSI-CKN-Pad87)") (class "Default")
      (node (ref "U1") (pin "87") (pinfunction "MCSI-CKN_87") (pintype "passive+no_connect"))
    )
    (net (code "101") (name "unconnected-(U1-MCSI-CKP-Pad86)") (class "Default")
      (node (ref "U1") (pin "86") (pinfunction "MCSI-CKP_86") (pintype "passive+no_connect"))
    )
    (net (code "102") (name "unconnected-(U1-MCSI-D0N-Pad82)") (class "Default")
      (node (ref "U1") (pin "82") (pinfunction "MCSI-D0N_82") (pintype "passive+no_connect"))
    )
    (net (code "103") (name "unconnected-(U1-MCSI-D0P-Pad81)") (class "Default")
      (node (ref "U1") (pin "81") (pinfunction "MCSI-D0P_81") (pintype "passive+no_connect"))
    )
    (net (code "104") (name "unconnected-(U1-MCSI-D1N-Pad84)") (class "Default")
      (node (ref "U1") (pin "84") (pinfunction "MCSI-D1N_84") (pintype "passive+no_connect"))
    )
    (net (code "105") (name "unconnected-(U1-MCSI-D1P-Pad83)") (class "Default")
      (node (ref "U1") (pin "83") (pinfunction "MCSI-D1P_83") (pintype "passive+no_connect"))
    )
    (net (code "106") (name "unconnected-(U1-PB2{slash}UART2_RTS{slash}PB_EINT2-Pad41)") (class "Default")
      (node (ref "U1") (pin "41") (pinfunction "PB2/UART2_RTS/PB_EINT2_41") (pintype "passive"))
    )
    (net (code "107") (name "unconnected-(U1-PB6{slash}TWI0_SCK{slash}PB_EINT6-Pad45)") (class "Default")
      (node (ref "U1") (pin "45") (pinfunction "PB6/TWI0_SCK/PB_EINT6_45") (pintype "passive+no_connect"))
    )
    (net (code "108") (name "unconnected-(U1-PB7{slash}TWI0_SDA{slash}PB_EINT7-Pad46)") (class "Default")
      (node (ref "U1") (pin "46") (pinfunction "PB7/TWI0_SDA/PB_EINT7_46") (pintype "passive+no_connect"))
    )
    (net (code "109") (name "unconnected-(U1-PE0{slash}CSI_PCLK{slash}LCD_CLK-Pad37)") (class "Default")
      (node (ref "U1") (pin "37") (pinfunction "PE0/CSI_PCLK/LCD_CLK_37") (pintype "passive+no_connect"))
    )
    (net (code "110") (name "unconnected-(U1-PE1{slash}CSI_MCLK{slash}LCD_DE-Pad36)") (class "Default")
      (node (ref "U1") (pin "36") (pinfunction "PE1/CSI_MCLK/LCD_DE_36") (pintype "passive+no_connect"))
    )
    (net (code "111") (name "unconnected-(U1-PE2{slash}CSI_HSYNC{slash}LCD_HSYNC-Pad35)") (class "Default")
      (node (ref "U1") (pin "35") (pinfunction "PE2/CSI_HSYNC/LCD_HSYNC_35") (pintype "passive+no_connect"))
    )
    (net (code "112") (name "unconnected-(U1-PE3{slash}CSI_VSYNC{slash}LCD_VSYNC-Pad34)") (class "Default")
      (node (ref "U1") (pin "34") (pinfunction "PE3/CSI_VSYNC/LCD_VSYNC_34") (pintype "passive+no_connect"))
    )
    (net (code "113") (name "unconnected-(U1-PE4{slash}CSI_D0{slash}LCD_D2-Pad33)") (class "Default")
      (node (ref "U1") (pin "33") (pinfunction "PE4/CSI_D0/LCD_D2_33") (pintype "passive+no_connect"))
    )
    (net (code "114") (name "unconnected-(U1-PE5{slash}CSI_D1{slash}LCD_D3-Pad32)") (class "Default")
      (node (ref "U1") (pin "32") (pinfunction "PE5/CSI_D1/LCD_D3_32") (pintype "passive+no_connect"))
    )
    (net (code "115") (name "unconnected-(U1-PE6{slash}CSI_D2{slash}LCD_D4-Pad31)") (class "Default")
      (node (ref "U1") (pin "31") (pinfunction "PE6/CSI_D2/LCD_D4_31") (pintype "passive+no_connect"))
    )
    (net (code "116") (name "unconnected-(U1-PE7{slash}CSI_D3{slash}LCD_D5-Pad30)") (class "Default")
      (node (ref "U1") (pin "30") (pinfunction "PE7/CSI_D3/LCD_D5_30") (pintype "passive+no_connect"))
    )
    (net (code "117") (name "unconnected-(U1-PE8{slash}CSI_D4{slash}LCD_D6-Pad28)") (class "Default")
      (node (ref "U1") (pin "28") (pinfunction "PE8/CSI_D4/LCD_D6_28") (pintype "passive+no_connect"))
    )
    (net (code "118") (name "unconnected-(U1-PE9{slash}CSI_D5{slash}LCD_D7-Pad27)") (class "Default")
      (node (ref "U1") (pin "27") (pinfunction "PE9/CSI_D5/LCD_D7_27") (pintype "passive+no_connect"))
    )
    (net (code "119") (name "unconnected-(U1-PE10{slash}CSI_D6{slash}LCD_D10-Pad24)") (class "Default")
      (node (ref "U1") (pin "24") (pinfunction "PE10/CSI_D6/LCD_D10_24") (pintype "passive+no_connect"))
    )
    (net (code "120") (name "unconnected-(U1-PE11{slash}CSI_D7{slash}LCD_D11-Pad23)") (class "Default")
      (node (ref "U1") (pin "23") (pinfunction "PE11/CSI_D7/LCD_D11_23") (pintype "passive+no_connect"))
    )
    (net (code "121") (name "unconnected-(U1-PE12{slash}CSI_D8{slash}LCD_D12-Pad22)") (class "Default")
      (node (ref "U1") (pin "22") (pinfunction "PE12/CSI_D8/LCD_D12_22") (pintype "passive+no_connect"))
    )
    (net (code "122") (name "unconnected-(U1-PE13{slash}CSI_D9{slash}LCD_D13-Pad18)") (class "Default")
      (node (ref "U1") (pin "18") (pinfunction "PE13/CSI_D9/LCD_D13_18") (pintype "passive+no_connect"))
    )
    (net (code "123") (name "unconnected-(U1-PE14{slash}CSI_D10{slash}LCD_D14-Pad17)") (class "Default")
      (node (ref "U1") (pin "17") (pinfunction "PE14/CSI_D10/LCD_D14_17") (pintype "passive+no_connect"))
    )
    (net (code "124") (name "unconnected-(U1-PE15{slash}CSI_D11{slash}LCD_D15-Pad16)") (class "Default")
      (node (ref "U1") (pin "16") (pinfunction "PE15/CSI_D11/LCD_D15_16") (pintype "passive+no_connect"))
    )
    (net (code "125") (name "unconnected-(U1-PE16{slash}CSI_D12{slash}LCD_D18-Pad15)") (class "Default")
      (node (ref "U1") (pin "15") (pinfunction "PE16/CSI_D12/LCD_D18_15") (pintype "passive+no_connect"))
    )
    (net (code "126") (name "unconnected-(U1-PE17{slash}CSI_D13{slash}LCD_D19-Pad14)") (class "Default")
      (node (ref "U1") (pin "14") (pinfunction "PE17/CSI_D13/LCD_D19_14") (pintype "passive+no_connect"))
    )
    (net (code "127") (name "unconnected-(U1-PE18{slash}CSI_D14{slash}LCD_D20-Pad13)") (class "Default")
      (node (ref "U1") (pin "13") (pinfunction "PE18/CSI_D14/LCD_D20_13") (pintype "passive+no_connect"))
    )
    (net (code "128") (name "unconnected-(U1-PE19{slash}CSI_D15{slash}LCD_D21-Pad11)") (class "Default")
      (node (ref "U1") (pin "11") (pinfunction "PE19/CSI_D15/LCD_D21_11") (pintype "passive+no_connect"))
    )
    (net (code "129") (name "unconnected-(U1-PE20{slash}CSI_FIELD{slash}CSI_MIPI_MCLK-Pad10)") (class "Default")
      (node (ref "U1") (pin "10") (pinfunction "PE20/CSI_FIELD/CSI_MIPI_MCLK_10") (pintype "passive+no_connect"))
    )
    (net (code "130") (name "unconnected-(U1-PE21{slash}CSI_SCK{slash}TWI1_SCK{slash}UART1_TX-Pad9)") (class "Default")
      (node (ref "U1") (pin "9") (pinfunction "PE21/CSI_SCK/TWI1_SCK/UART1_TX_9") (pintype "passive+no_connect"))
    )
    (net (code "131") (name "unconnected-(U1-PE23{slash}LCD_D22-Pad7)") (class "Default")
      (node (ref "U1") (pin "7") (pinfunction "PE23/LCD_D22_7") (pintype "passive+no_connect"))
    )
    (net (code "132") (name "unconnected-(U1-PE24{slash}LCD_D23-Pad6)") (class "Default")
      (node (ref "U1") (pin "6") (pinfunction "PE24/LCD_D23_6") (pintype "passive+no_connect"))
    )
    (net (code "133") (name "unconnected-(U4-BT_HOST_WAKE-Pad7)") (class "Default")
      (node (ref "U4") (pin "7") (pinfunction "BT_HOST_WAKE_7") (pintype "passive"))
    )
    (net (code "134") (name "unconnected-(U4-BT_WAKE-Pad6)") (class "Default")
      (node (ref "U4") (pin "6") (pinfunction "BT_WAKE_6") (pintype "passive"))
    )
    (net (code "135") (name "unconnected-(U4-NC1-Pad4)") (class "Default")
      (node (ref "U4") (pin "4") (pinfunction "NC1_4") (pintype "passive"))
    )
    (net (code "136") (name "unconnected-(U4-NC2-Pad5)") (class "Default")
      (node (ref "U4") (pin "5") (pinfunction "NC2_5") (pintype "passive"))
    )
    (net (code "137") (name "unconnected-(U4-NC3-Pad8)") (class "Default")
      (node (ref "U4") (pin "8") (pinfunction "NC3_8") (pintype "passive"))
    )
    (net (code "138") (name "unconnected-(U4-NC4-Pad10)") (class "Default")
      (node (ref "U4") (pin "10") (pinfunction "NC4_10") (pintype "passive"))
    )
    (net (code "139") (name "unconnected-(U4-NC5-Pad11)") (class "Default")
      (node (ref "U4") (pin "11") (pinfunction "NC5_11") (pintype "passive"))
    )
    (net (code "140") (name "unconnected-(U4-NC6-Pad21)") (class "Default")
      (node (ref "U4") (pin "21") (pinfunction "NC6_21") (pintype "passive"))
    )
    (net (code "141") (name "unconnected-(U4-NC7-Pad23)") (class "Default")
      (node (ref "U4") (pin "23") (pinfunction "NC7_23") (pintype "passive"))
    )
    (net (code "142") (name "unconnected-(U4-NC8-Pad29)") (class "Default")
      (node (ref "U4") (pin "29") (pinfunction "NC8_29") (pintype "passive"))
    )
    (net (code "143") (name "unconnected-(U4-NC9-Pad30)") (class "Default")
      (node (ref "U4") (pin "30") (pinfunction "NC9_30") (pintype "passive"))
    )
    (net (code "144") (name "unconnected-(U4-NC10-Pad32)") (class "Default")
      (node (ref "U4") (pin "32") (pinfunction "NC10_32") (pintype "passive"))
    )
    (net (code "145") (name "unconnected-(U4-NC11-Pad35)") (class "Default")
      (node (ref "U4") (pin "35") (pinfunction "NC11_35") (pintype "passive"))
    )
    (net (code "146") (name "unconnected-(U4-NC12-Pad37)") (class "Default")
      (node (ref "U4") (pin "37") (pinfunction "NC12_37") (pintype "passive"))
    )
    (net (code "147") (name "unconnected-(U4-NC13-Pad38)") (class "Default")
      (node (ref "U4") (pin "38") (pinfunction "NC13_38") (pintype "passive"))
    )
    (net (code "148") (name "unconnected-(U4-NC14-Pad39)") (class "Default")
      (node (ref "U4") (pin "39") (pinfunction "NC14_39") (pintype "passive"))
    )
    (net (code "149") (name "unconnected-(U4-NC15-Pad40)") (class "Default")
      (node (ref "U4") (pin "40") (pinfunction "NC15_40") (pintype "passive"))
    )
    (net (code "150") (name "unconnected-(U4-PCM_CLK-Pad26)") (class "Default")
      (node (ref "U4") (pin "26") (pinfunction "PCM_CLK_26") (pintype "passive"))
    )
    (net (code "151") (name "unconnected-(U4-PCM_DIN-Pad27)") (class "Default")
      (node (ref "U4") (pin "27") (pinfunction "PCM_DIN_27") (pintype "passive"))
    )
    (net (code "152") (name "unconnected-(U4-PCM_DOUT-Pad25)") (class "Default")
      (node (ref "U4") (pin "25") (pinfunction "PCM_DOUT_25") (pintype "passive"))
    )
    (net (code "153") (name "unconnected-(U4-PCM_SYNC-Pad28)") (class "Default")
      (node (ref "U4") (pin "28") (pinfunction "PCM_SYNC_28") (pintype "passive"))
    )
    (net (code "154") (name "unconnected-(U4-SUBSCLK_IN-Pad24)") (class "Default")
      (node (ref "U4") (pin "24") (pinfunction "SUBSCLK_IN_24") (pintype "passive"))
    )
    (net (code "155") (name "unconnected-(U5-NC-Pad3)") (class "Default")
      (node (ref "U5") (pin "3") (pinfunction "NC_3") (pintype "passive+no_connect"))
    )
    (net (code "156") (name "unconnected-(U6-NC-Pad3)") (class "Default")
      (node (ref "U6") (pin "3") (pinfunction "NC_3") (pintype "passive+no_connect"))
    )
    (net (code "157") (name "unconnected-(U7-CTS#-Pad5)") (class "Default")
      (node (ref "U7") (pin "5") (pinfunction "CTS#_5") (pintype "passive"))
    )
    (net (code "158") (name "unconnected-(U7-RTS#-Pad4)") (class "Default")
      (node (ref "U7") (pin "4") (pinfunction "RTS#_4") (pintype "passive"))
    )
    (net (code "159") (name "unconnected-(U7-TNOW-Pad6)") (class "Default")
      (node (ref "U7") (pin "6") (pinfunction "TNOW_6") (pintype "passive"))
    )
  )
)
